# Schematics_EasyEDA.net
KiCad netlist of a schematic drawn in EasyEDA
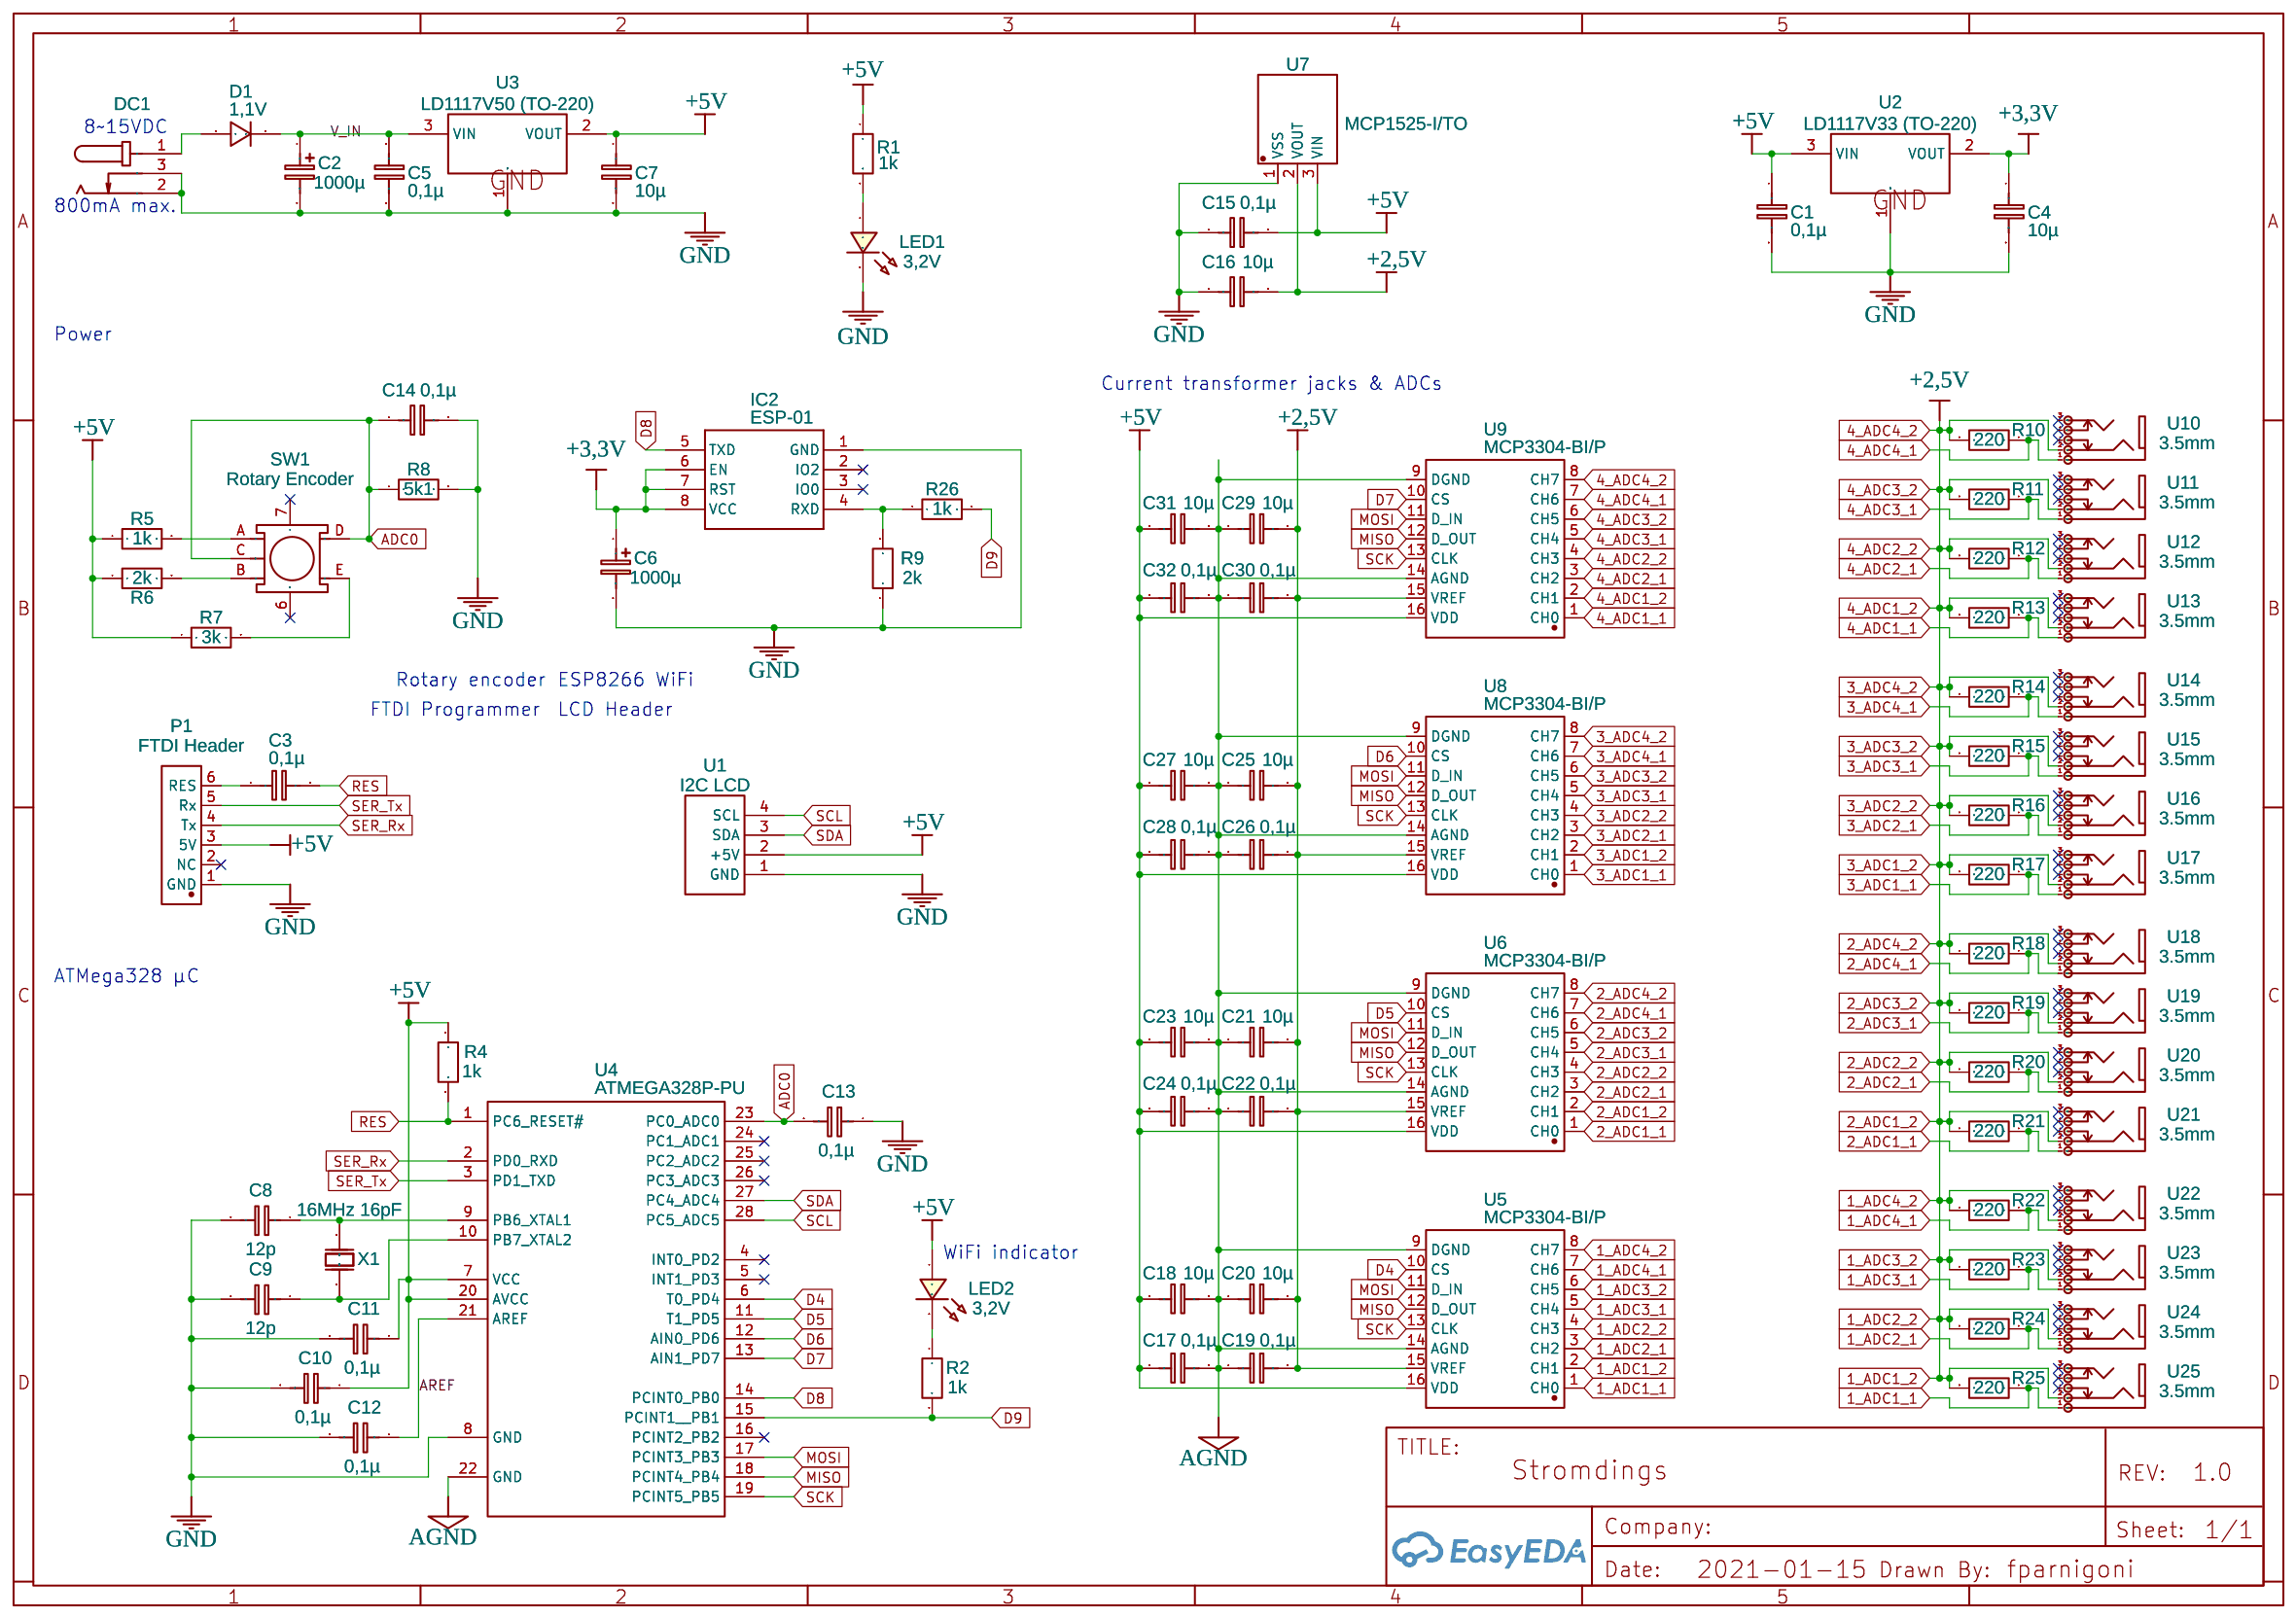
[diagram p0: schematic sheet]

(export (version "E")
  (design (tool "Eeschema 10.0.6"))
  (components
    (comp (ref "C1") (value "0,1µ") (libsource (lib "") (part "C_0603_EU_6")))
    (comp (ref "C2") (value "1000µ") (libsource (lib "") (part "C_Tan_SMD_A_EU_1")))
    (comp (ref "C3") (value "0,1µ") (libsource (lib "") (part "C_0603_EU_5")))
    (comp (ref "C4") (value "10µ") (libsource (lib "") (part "C_0603_EU_6")))
    (comp (ref "C5") (value "0,1µ") (libsource (lib "") (part "C_0603_EU_7")))
    (comp (ref "C6") (value "1000µ") (libsource (lib "") (part "C_Tan_SMD_A_EU")))
    (comp (ref "C7") (value "10µ") (libsource (lib "") (part "C_0603_EU_7")))
    (comp (ref "C8") (value "12p") (libsource (lib "") (part "C_0603_EU_2")))
    (comp (ref "C9") (value "12p") (libsource (lib "") (part "C_0603_EU_2")))
    (comp (ref "C10") (value "0,1µ") (libsource (lib "") (part "C_0603_EU_8")))
    (comp (ref "C11") (value "0,1µ") (libsource (lib "") (part "C_0603_EU_3")))
    (comp (ref "C12") (value "0,1µ") (libsource (lib "") (part "C_0603_EU_8")))
    (comp (ref "C13") (value "0,1µ") (libsource (lib "") (part "C_0603_EU_3")))
    (comp (ref "C14") (value "0,1µ") (libsource (lib "") (part "C_0603_EU_4")))
    (comp (ref "C15") (value "0,1µ") (libsource (lib "") (part "C_0603_EU_1")))
    (comp (ref "C16") (value "10µ") (libsource (lib "") (part "C_0603_EU_1")))
    (comp (ref "C17") (value "0,1µ") (libsource (lib "") (part "C_0603_EU_1")))
    (comp (ref "C18") (value "10µ") (libsource (lib "") (part "C_0603_EU")))
    (comp (ref "C19") (value "0,1µ") (libsource (lib "") (part "C_0603_EU_1")))
    (comp (ref "C20") (value "10µ") (libsource (lib "") (part "C_0603_EU")))
    (comp (ref "C21") (value "10µ") (libsource (lib "") (part "C_0603_EU")))
    (comp (ref "C22") (value "0,1µ") (libsource (lib "") (part "C_0603_EU")))
    (comp (ref "C23") (value "10µ") (libsource (lib "") (part "C_0603_EU")))
    (comp (ref "C24") (value "0,1µ") (libsource (lib "") (part "C_0603_EU")))
    (comp (ref "C25") (value "10µ") (libsource (lib "") (part "C_0603_EU")))
    (comp (ref "C26") (value "0,1µ") (libsource (lib "") (part "C_0603_EU")))
    (comp (ref "C27") (value "10µ") (libsource (lib "") (part "C_0603_EU")))
    (comp (ref "C28") (value "0,1µ") (libsource (lib "") (part "C_0603_EU")))
    (comp (ref "C29") (value "10µ") (libsource (lib "") (part "C_0603_EU_1")))
    (comp (ref "C30") (value "0,1µ") (libsource (lib "") (part "C_0603_EU")))
    (comp (ref "C31") (value "10µ") (libsource (lib "") (part "C_0603_EU_1")))
    (comp (ref "C32") (value "0,1µ") (libsource (lib "") (part "C_0603_EU")))
    (comp (ref "D1")
      (value "1,1V")
      (fields (field (name "BOM_Manufacturer Part") "1N4007W") (field (name "BOM_Supplier Part") "C328592"))
      (libsource (lib "") (part "1N4007W"))
    )
    (comp (ref "DC1")
      (value "DC005-2.0MM")
      (fields (field (name "BOM_Supplier Part") "C111567"))
      (libsource (lib "") (part "DC005-2.0MM"))
    )
    (comp (ref "IC2") (value "ESP-01") (libsource (lib "") (part "ESP-01")))
    (comp (ref "LED1")
      (value "3,2V")
      (fields
        (field (name "BOM_Manufacturer Part") "D-B080508B1-KS2")
        (field (name "BOM_Supplier Part") "C108412")
      )
      (libsource (lib "") (part "LED-0805_B"))
    )
    (comp (ref "LED2")
      (value "3,2V")
      (fields
        (field (name "BOM_Manufacturer Part") "D-B080508B1-KS2")
        (field (name "BOM_Supplier Part") "C108412")
      )
      (libsource (lib "") (part "LED-0805_B"))
    )
    (comp (ref "P1")
      (value "FTDI Header")
      (fields
        (field (name "BOM_Manufacturer Part") "Female header 1*6p")
        (field (name "BOM_Supplier Part") "C40877")
      )
      (libsource (lib "") (part "Header-Female-2.54_1x6"))
    )
    (comp (ref "R1") (value "1k") (libsource (lib "") (part "R_0603_EU_2")))
    (comp (ref "R2") (value "1k") (libsource (lib "") (part "R_0603_EU_2")))
    (comp (ref "R4") (value "1k") (libsource (lib "") (part "R_0603_EU_2")))
    (comp (ref "R5") (value "1k") (libsource (lib "") (part "R_0603_EU")))
    (comp (ref "R6") (value "2k") (libsource (lib "") (part "R_0603_EU")))
    (comp (ref "R7") (value "3k") (libsource (lib "") (part "R_0603_EU")))
    (comp (ref "R8") (value "5k1") (libsource (lib "") (part "R_0603_EU")))
    (comp (ref "R9") (value "2k") (libsource (lib "") (part "R_0603_EU_3")))
    (comp (ref "R10") (value "220") (libsource (lib "") (part "R_0603_EU_1")))
    (comp (ref "R11") (value "220") (libsource (lib "") (part "R_0603_EU_1")))
    (comp (ref "R12") (value "220") (libsource (lib "") (part "R_0603_EU_1")))
    (comp (ref "R13") (value "220") (libsource (lib "") (part "R_0603_EU_1")))
    (comp (ref "R14") (value "220") (libsource (lib "") (part "R_0603_EU_1")))
    (comp (ref "R15") (value "220") (libsource (lib "") (part "R_0603_EU_1")))
    (comp (ref "R16") (value "220") (libsource (lib "") (part "R_0603_EU_1")))
    (comp (ref "R17") (value "220") (libsource (lib "") (part "R_0603_EU_1")))
    (comp (ref "R18") (value "220") (libsource (lib "") (part "R_0603_EU_1")))
    (comp (ref "R19") (value "220") (libsource (lib "") (part "R_0603_EU_1")))
    (comp (ref "R20") (value "220") (libsource (lib "") (part "R_0603_EU_1")))
    (comp (ref "R21") (value "220") (libsource (lib "") (part "R_0603_EU_1")))
    (comp (ref "R22") (value "220") (libsource (lib "") (part "R_0603_EU_1")))
    (comp (ref "R23") (value "220") (libsource (lib "") (part "R_0603_EU_1")))
    (comp (ref "R24") (value "220") (libsource (lib "") (part "R_0603_EU_1")))
    (comp (ref "R25") (value "220") (libsource (lib "") (part "R_0603_EU_1")))
    (comp (ref "R26") (value "1k") (libsource (lib "") (part "R_0603_EU")))
    (comp (ref "SW1")
      (value "Rotary Encoder")
      (fields
        (field (name "BOM_Manufacturer Part") "EC11E09244BS")
        (field (name "BOM_Supplier Part") "C470742")
      )
      (libsource (lib "") (part "EC11E09244BS"))
    )
    (comp (ref "U1") (value "I2C LCD") (libsource (lib "") (part "I2C LCD")))
    (comp (ref "U2")
      (value "LD1117V33 (TO-220)")
      (fields (field (name "BOM_Manufacturer Part") "LD1117V33") (field (name "BOM_Supplier Part") "C283467"))
      (libsource (lib "") (part "LD1117V33"))
    )
    (comp (ref "U3")
      (value "LD1117V50 (TO-220)")
      (fields (field (name "BOM_Manufacturer Part") "LD1117V33") (field (name "BOM_Supplier Part") "C283467"))
      (libsource (lib "") (part "LD1117V33"))
    )
    (comp (ref "U4")
      (value "ATMEGA328P-PU")
      (fields (field (name "BOM_Supplier Part") "C33901"))
      (libsource (lib "") (part "ATMEGA328P-PU"))
    )
    (comp (ref "U5") (value "MCP3304-BI/P") (libsource (lib "") (part "MCP3304-BI/P")))
    (comp (ref "U6") (value "MCP3304-BI/P") (libsource (lib "") (part "MCP3304-BI/P")))
    (comp (ref "U7")
      (value "MCP1525-I/TO")
      (fields (field (name "BOM_Supplier Part") "C184389"))
      (libsource (lib "") (part "MCP1525-I/TO"))
    )
    (comp (ref "U8") (value "MCP3304-BI/P") (libsource (lib "") (part "MCP3304-BI/P")))
    (comp (ref "U9") (value "MCP3304-BI/P") (libsource (lib "") (part "MCP3304-BI/P")))
    (comp (ref "U10") (value "3.5mm") (libsource (lib "") (part "Unknown_1060_-590")))
    (comp (ref "U11") (value "3.5mm") (libsource (lib "") (part "Unknown_1060_-560")))
    (comp (ref "U12") (value "3.5mm") (libsource (lib "") (part "Unknown_1060_-530")))
    (comp (ref "U13") (value "3.5mm") (libsource (lib "") (part "Unknown_1060_-500")))
    (comp (ref "U14") (value "3.5mm") (libsource (lib "") (part "Unknown_1060_-460")))
    (comp (ref "U15") (value "3.5mm") (libsource (lib "") (part "Unknown_1060_-430")))
    (comp (ref "U16") (value "3.5mm") (libsource (lib "") (part "Unknown_1060_-400")))
    (comp (ref "U17") (value "3.5mm") (libsource (lib "") (part "Unknown_1060_-370")))
    (comp (ref "U18") (value "3.5mm") (libsource (lib "") (part "Unknown_1060_-330")))
    (comp (ref "U19") (value "3.5mm") (libsource (lib "") (part "Unknown_1060_-300")))
    (comp (ref "U20") (value "3.5mm") (libsource (lib "") (part "Unknown_1060_-270")))
    (comp (ref "U21") (value "3.5mm") (libsource (lib "") (part "Unknown_1060_-240")))
    (comp (ref "U22") (value "3.5mm") (libsource (lib "") (part "Unknown_1060_-200")))
    (comp (ref "U23") (value "3.5mm") (libsource (lib "") (part "Unknown_1060_-170")))
    (comp (ref "U24") (value "3.5mm") (libsource (lib "") (part "Unknown_1060_-140")))
    (comp (ref "U25") (value "3.5mm") (libsource (lib "") (part "Unknown_1060_-110")))
    (comp (ref "X1")
      (value "16MHz 16pF")
      (fields
        (field (name "BOM_Manufacturer Part") "HCM4916000000ABJT")
        (field (name "BOM_Supplier Part") "C326544")
      )
      (libsource (lib "") (part "HCM4916000000ABJT"))
    )
  )
  (nets
    (net (code "1") (name "+3,3V") (class "Default")
      (node (ref "C4") (pin "1") (pinfunction "1_1") (pintype "unspecified"))
      (node (ref "C6") (pin "1") (pinfunction "1_1") (pintype "unspecified"))
      (node (ref "IC2") (pin "6") (pinfunction "EN_6") (pintype "bidirectional"))
      (node (ref "IC2") (pin "7") (pinfunction "RST_7") (pintype "bidirectional"))
      (node (ref "IC2") (pin "8") (pinfunction "VCC_8") (pintype "bidirectional"))
      (node (ref "U2") (pin "2") (pinfunction "VOUT_2") (pintype "passive"))
    )
    (net (code "2") (name "+5V") (class "Default")
      (node (ref "C1") (pin "1") (pinfunction "1_1") (pintype "unspecified"))
      (node (ref "C10") (pin "1") (pinfunction "1_1") (pintype "unspecified"))
      (node (ref "C11") (pin "1") (pinfunction "1_1") (pintype "unspecified"))
      (node (ref "C15") (pin "2") (pinfunction "2_2") (pintype "unspecified"))
      (node (ref "C17") (pin "1") (pinfunction "1_1") (pintype "unspecified"))
      (node (ref "C18") (pin "1") (pinfunction "1_1") (pintype "unspecified"))
      (node (ref "C23") (pin "1") (pinfunction "1_1") (pintype "unspecified"))
      (node (ref "C24") (pin "1") (pinfunction "1_1") (pintype "unspecified"))
      (node (ref "C27") (pin "1") (pinfunction "1_1") (pintype "unspecified"))
      (node (ref "C28") (pin "1") (pinfunction "1_1") (pintype "unspecified"))
      (node (ref "C31") (pin "1") (pinfunction "1_1") (pintype "unspecified"))
      (node (ref "C32") (pin "1") (pinfunction "1_1") (pintype "unspecified"))
      (node (ref "C7") (pin "1") (pinfunction "1_1") (pintype "unspecified"))
      (node (ref "LED2") (pin "1") (pinfunction "1_1") (pintype "unspecified"))
      (node (ref "P1") (pin "3") (pinfunction "5V_3") (pintype "unspecified"))
      (node (ref "R1") (pin "1") (pinfunction "1_1") (pintype "unspecified"))
      (node (ref "R4") (pin "1") (pinfunction "1_1") (pintype "unspecified"))
      (node (ref "R5") (pin "1") (pinfunction "1_1") (pintype "unspecified"))
      (node (ref "R6") (pin "1") (pinfunction "1_1") (pintype "unspecified"))
      (node (ref "R7") (pin "1") (pinfunction "1_1") (pintype "unspecified"))
      (node (ref "U1") (pin "2") (pinfunction "+5V_2") (pintype "unspecified"))
      (node (ref "U2") (pin "3") (pinfunction "VIN_3") (pintype "passive"))
      (node (ref "U3") (pin "2") (pinfunction "VOUT_2") (pintype "passive"))
      (node (ref "U4") (pin "20") (pinfunction "AVCC_20") (pintype "passive"))
      (node (ref "U4") (pin "7") (pinfunction "VCC_7") (pintype "passive"))
      (node (ref "U5") (pin "16") (pinfunction "VDD_16") (pintype "unspecified"))
      (node (ref "U6") (pin "16") (pinfunction "VDD_16") (pintype "unspecified"))
      (node (ref "U7") (pin "3") (pinfunction "VIN_3") (pintype "unspecified"))
      (node (ref "U8") (pin "16") (pinfunction "VDD_16") (pintype "unspecified"))
      (node (ref "U9") (pin "16") (pinfunction "VDD_16") (pintype "unspecified"))
    )
    (net (code "3") (name "/AREF") (class "Default")
      (node (ref "C12") (pin "1") (pinfunction "1_1") (pintype "unspecified"))
      (node (ref "U4") (pin "21") (pinfunction "AREF_21") (pintype "passive"))
    )
    (net (code "4") (name "/V_IN") (class "Default")
      (node (ref "C2") (pin "1") (pinfunction "1_1") (pintype "unspecified"))
      (node (ref "C5") (pin "1") (pinfunction "1_1") (pintype "unspecified"))
      (node (ref "D1") (pin "1") (pinfunction "1_1") (pintype "unspecified"))
      (node (ref "U3") (pin "3") (pinfunction "VIN_3") (pintype "passive"))
    )
    (net (code "5") (name "1_ADC1_1") (class "Default")
      (node (ref "R25") (pin "1") (pinfunction "1_1") (pintype "unspecified"))
      (node (ref "U25") (pin "1") (pinfunction "SLV_1") (pintype "input"))
      (node (ref "U5") (pin "1") (pinfunction "CH0_1") (pintype "unspecified"))
    )
    (net (code "6") (name "1_ADC1_2") (class "Default")
      (node (ref "C16") (pin "2") (pinfunction "2_2") (pintype "unspecified"))
      (node (ref "C19") (pin "2") (pinfunction "2_2") (pintype "unspecified"))
      (node (ref "C20") (pin "2") (pinfunction "2_2") (pintype "unspecified"))
      (node (ref "C21") (pin "2") (pinfunction "2_2") (pintype "unspecified"))
      (node (ref "C22") (pin "2") (pinfunction "2_2") (pintype "unspecified"))
      (node (ref "C25") (pin "2") (pinfunction "2_2") (pintype "unspecified"))
      (node (ref "C26") (pin "2") (pinfunction "2_2") (pintype "unspecified"))
      (node (ref "C29") (pin "2") (pinfunction "2_2") (pintype "unspecified"))
      (node (ref "C30") (pin "2") (pinfunction "2_2") (pintype "unspecified"))
      (node (ref "R10") (pin "2") (pinfunction "2_2") (pintype "unspecified"))
      (node (ref "R11") (pin "2") (pinfunction "2_2") (pintype "unspecified"))
      (node (ref "R12") (pin "2") (pinfunction "2_2") (pintype "unspecified"))
      (node (ref "R13") (pin "2") (pinfunction "2_2") (pintype "unspecified"))
      (node (ref "R14") (pin "2") (pinfunction "2_2") (pintype "unspecified"))
      (node (ref "R15") (pin "2") (pinfunction "2_2") (pintype "unspecified"))
      (node (ref "R16") (pin "2") (pinfunction "2_2") (pintype "unspecified"))
      (node (ref "R17") (pin "2") (pinfunction "2_2") (pintype "unspecified"))
      (node (ref "R18") (pin "2") (pinfunction "2_2") (pintype "unspecified"))
      (node (ref "R19") (pin "2") (pinfunction "2_2") (pintype "unspecified"))
      (node (ref "R20") (pin "2") (pinfunction "2_2") (pintype "unspecified"))
      (node (ref "R21") (pin "2") (pinfunction "2_2") (pintype "unspecified"))
      (node (ref "R22") (pin "2") (pinfunction "2_2") (pintype "unspecified"))
      (node (ref "R23") (pin "2") (pinfunction "2_2") (pintype "unspecified"))
      (node (ref "R24") (pin "2") (pinfunction "2_2") (pintype "unspecified"))
      (node (ref "R25") (pin "2") (pinfunction "2_2") (pintype "unspecified"))
      (node (ref "U10") (pin "2") (pinfunction "TIP_2") (pintype "input"))
      (node (ref "U11") (pin "2") (pinfunction "TIP_2") (pintype "input"))
      (node (ref "U12") (pin "2") (pinfunction "TIP_2") (pintype "input"))
      (node (ref "U13") (pin "2") (pinfunction "TIP_2") (pintype "input"))
      (node (ref "U14") (pin "2") (pinfunction "TIP_2") (pintype "input"))
      (node (ref "U15") (pin "2") (pinfunction "TIP_2") (pintype "input"))
      (node (ref "U16") (pin "2") (pinfunction "TIP_2") (pintype "input"))
      (node (ref "U17") (pin "2") (pinfunction "TIP_2") (pintype "input"))
      (node (ref "U18") (pin "2") (pinfunction "TIP_2") (pintype "input"))
      (node (ref "U19") (pin "2") (pinfunction "TIP_2") (pintype "input"))
      (node (ref "U20") (pin "2") (pinfunction "TIP_2") (pintype "input"))
      (node (ref "U21") (pin "2") (pinfunction "TIP_2") (pintype "input"))
      (node (ref "U22") (pin "2") (pinfunction "TIP_2") (pintype "input"))
      (node (ref "U23") (pin "2") (pinfunction "TIP_2") (pintype "input"))
      (node (ref "U24") (pin "2") (pinfunction "TIP_2") (pintype "input"))
      (node (ref "U25") (pin "2") (pinfunction "TIP_2") (pintype "input"))
      (node (ref "U5") (pin "15") (pinfunction "VREF_15") (pintype "unspecified"))
      (node (ref "U5") (pin "2") (pinfunction "CH1_2") (pintype "unspecified"))
      (node (ref "U5") (pin "4") (pinfunction "CH3_4") (pintype "unspecified"))
      (node (ref "U5") (pin "6") (pinfunction "CH5_6") (pintype "unspecified"))
      (node (ref "U5") (pin "8") (pinfunction "CH7_8") (pintype "unspecified"))
      (node (ref "U6") (pin "15") (pinfunction "VREF_15") (pintype "unspecified"))
      (node (ref "U6") (pin "2") (pinfunction "CH1_2") (pintype "unspecified"))
      (node (ref "U6") (pin "4") (pinfunction "CH3_4") (pintype "unspecified"))
      (node (ref "U6") (pin "6") (pinfunction "CH5_6") (pintype "unspecified"))
      (node (ref "U6") (pin "8") (pinfunction "CH7_8") (pintype "unspecified"))
      (node (ref "U7") (pin "2") (pinfunction "VOUT_2") (pintype "unspecified"))
      (node (ref "U8") (pin "15") (pinfunction "VREF_15") (pintype "unspecified"))
      (node (ref "U8") (pin "2") (pinfunction "CH1_2") (pintype "unspecified"))
      (node (ref "U8") (pin "4") (pinfunction "CH3_4") (pintype "unspecified"))
      (node (ref "U8") (pin "6") (pinfunction "CH5_6") (pintype "unspecified"))
      (node (ref "U8") (pin "8") (pinfunction "CH7_8") (pintype "unspecified"))
      (node (ref "U9") (pin "15") (pinfunction "VREF_15") (pintype "unspecified"))
      (node (ref "U9") (pin "2") (pinfunction "CH1_2") (pintype "unspecified"))
      (node (ref "U9") (pin "4") (pinfunction "CH3_4") (pintype "unspecified"))
      (node (ref "U9") (pin "6") (pinfunction "CH5_6") (pintype "unspecified"))
      (node (ref "U9") (pin "8") (pinfunction "CH7_8") (pintype "unspecified"))
    )
    (net (code "7") (name "1_ADC2_1") (class "Default")
      (node (ref "R24") (pin "1") (pinfunction "1_1") (pintype "unspecified"))
      (node (ref "U24") (pin "1") (pinfunction "SLV_1") (pintype "input"))
      (node (ref "U5") (pin "3") (pinfunction "CH2_3") (pintype "unspecified"))
    )
    (net (code "8") (name "1_ADC3_1") (class "Default")
      (node (ref "R23") (pin "1") (pinfunction "1_1") (pintype "unspecified"))
      (node (ref "U23") (pin "1") (pinfunction "SLV_1") (pintype "input"))
      (node (ref "U5") (pin "5") (pinfunction "CH4_5") (pintype "unspecified"))
    )
    (net (code "9") (name "1_ADC4_1") (class "Default")
      (node (ref "R22") (pin "1") (pinfunction "1_1") (pintype "unspecified"))
      (node (ref "U22") (pin "1") (pinfunction "SLV_1") (pintype "input"))
      (node (ref "U5") (pin "7") (pinfunction "CH6_7") (pintype "unspecified"))
    )
    (net (code "10") (name "2_ADC1_1") (class "Default")
      (node (ref "R21") (pin "1") (pinfunction "1_1") (pintype "unspecified"))
      (node (ref "U21") (pin "1") (pinfunction "SLV_1") (pintype "input"))
      (node (ref "U6") (pin "1") (pinfunction "CH0_1") (pintype "unspecified"))
    )
    (net (code "11") (name "2_ADC2_1") (class "Default")
      (node (ref "R20") (pin "1") (pinfunction "1_1") (pintype "unspecified"))
      (node (ref "U20") (pin "1") (pinfunction "SLV_1") (pintype "input"))
      (node (ref "U6") (pin "3") (pinfunction "CH2_3") (pintype "unspecified"))
    )
    (net (code "12") (name "2_ADC3_1") (class "Default")
      (node (ref "R19") (pin "1") (pinfunction "1_1") (pintype "unspecified"))
      (node (ref "U19") (pin "1") (pinfunction "SLV_1") (pintype "input"))
      (node (ref "U6") (pin "5") (pinfunction "CH4_5") (pintype "unspecified"))
    )
    (net (code "13") (name "2_ADC4_1") (class "Default")
      (node (ref "R18") (pin "1") (pinfunction "1_1") (pintype "unspecified"))
      (node (ref "U18") (pin "1") (pinfunction "SLV_1") (pintype "input"))
      (node (ref "U6") (pin "7") (pinfunction "CH6_7") (pintype "unspecified"))
    )
    (net (code "14") (name "3_ADC1_1") (class "Default")
      (node (ref "R17") (pin "1") (pinfunction "1_1") (pintype "unspecified"))
      (node (ref "U17") (pin "1") (pinfunction "SLV_1") (pintype "input"))
      (node (ref "U8") (pin "1") (pinfunction "CH0_1") (pintype "unspecified"))
    )
    (net (code "15") (name "3_ADC2_1") (class "Default")
      (node (ref "R16") (pin "1") (pinfunction "1_1") (pintype "unspecified"))
      (node (ref "U16") (pin "1") (pinfunction "SLV_1") (pintype "input"))
      (node (ref "U8") (pin "3") (pinfunction "CH2_3") (pintype "unspecified"))
    )
    (net (code "16") (name "3_ADC3_1") (class "Default")
      (node (ref "R15") (pin "1") (pinfunction "1_1") (pintype "unspecified"))
      (node (ref "U15") (pin "1") (pinfunction "SLV_1") (pintype "input"))
      (node (ref "U8") (pin "5") (pinfunction "CH4_5") (pintype "unspecified"))
    )
    (net (code "17") (name "3_ADC4_1") (class "Default")
      (node (ref "R14") (pin "1") (pinfunction "1_1") (pintype "unspecified"))
      (node (ref "U14") (pin "1") (pinfunction "SLV_1") (pintype "input"))
      (node (ref "U8") (pin "7") (pinfunction "CH6_7") (pintype "unspecified"))
    )
    (net (code "18") (name "4_ADC1_1") (class "Default")
      (node (ref "R13") (pin "1") (pinfunction "1_1") (pintype "unspecified"))
      (node (ref "U13") (pin "1") (pinfunction "SLV_1") (pintype "input"))
      (node (ref "U9") (pin "1") (pinfunction "CH0_1") (pintype "unspecified"))
    )
    (net (code "19") (name "4_ADC2_1") (class "Default")
      (node (ref "R12") (pin "1") (pinfunction "1_1") (pintype "unspecified"))
      (node (ref "U12") (pin "1") (pinfunction "SLV_1") (pintype "input"))
      (node (ref "U9") (pin "3") (pinfunction "CH2_3") (pintype "unspecified"))
    )
    (net (code "20") (name "4_ADC3_1") (class "Default")
      (node (ref "R11") (pin "1") (pinfunction "1_1") (pintype "unspecified"))
      (node (ref "U11") (pin "1") (pinfunction "SLV_1") (pintype "input"))
      (node (ref "U9") (pin "5") (pinfunction "CH4_5") (pintype "unspecified"))
    )
    (net (code "21") (name "4_ADC4_1") (class "Default")
      (node (ref "R10") (pin "1") (pinfunction "1_1") (pintype "unspecified"))
      (node (ref "U10") (pin "1") (pinfunction "SLV_1") (pintype "input"))
      (node (ref "U9") (pin "7") (pinfunction "CH6_7") (pintype "unspecified"))
    )
    (net (code "22") (name "ADC0") (class "Default")
      (node (ref "C13") (pin "2") (pinfunction "2_2") (pintype "unspecified"))
      (node (ref "C14") (pin "1") (pinfunction "1_1") (pintype "unspecified"))
      (node (ref "R8") (pin "1") (pinfunction "1_1") (pintype "unspecified"))
      (node (ref "SW1") (pin "C") (pinfunction "C_C") (pintype "unspecified"))
      (node (ref "SW1") (pin "D") (pinfunction "D_D") (pintype "unspecified"))
      (node (ref "U4") (pin "23") (pinfunction "PC0_ADC0_23") (pintype "bidirectional"))
    )
    (net (code "23") (name "AGND") (class "Default")
      (node (ref "C17") (pin "2") (pinfunction "2_2") (pintype "unspecified"))
      (node (ref "C18") (pin "2") (pinfunction "2_2") (pintype "unspecified"))
      (node (ref "C19") (pin "1") (pinfunction "1_1") (pintype "unspecified"))
      (node (ref "C20") (pin "1") (pinfunction "1_1") (pintype "unspecified"))
      (node (ref "C21") (pin "1") (pinfunction "1_1") (pintype "unspecified"))
      (node (ref "C22") (pin "1") (pinfunction "1_1") (pintype "unspecified"))
      (node (ref "C23") (pin "2") (pinfunction "2_2") (pintype "unspecified"))
      (node (ref "C24") (pin "2") (pinfunction "2_2") (pintype "unspecified"))
      (node (ref "C25") (pin "1") (pinfunction "1_1") (pintype "unspecified"))
      (node (ref "C26") (pin "1") (pinfunction "1_1") (pintype "unspecified"))
      (node (ref "C27") (pin "2") (pinfunction "2_2") (pintype "unspecified"))
      (node (ref "C28") (pin "2") (pinfunction "2_2") (pintype "unspecified"))
      (node (ref "C29") (pin "1") (pinfunction "1_1") (pintype "unspecified"))
      (node (ref "C30") (pin "1") (pinfunction "1_1") (pintype "unspecified"))
      (node (ref "C31") (pin "2") (pinfunction "2_2") (pintype "unspecified"))
      (node (ref "C32") (pin "2") (pinfunction "2_2") (pintype "unspecified"))
      (node (ref "U4") (pin "22") (pinfunction "GND_22") (pintype "passive"))
      (node (ref "U5") (pin "14") (pinfunction "AGND_14") (pintype "unspecified"))
      (node (ref "U5") (pin "9") (pinfunction "DGND_9") (pintype "unspecified"))
      (node (ref "U6") (pin "14") (pinfunction "AGND_14") (pintype "unspecified"))
      (node (ref "U6") (pin "9") (pinfunction "DGND_9") (pintype "unspecified"))
      (node (ref "U8") (pin "14") (pinfunction "AGND_14") (pintype "unspecified"))
      (node (ref "U8") (pin "9") (pinfunction "DGND_9") (pintype "unspecified"))
      (node (ref "U9") (pin "14") (pinfunction "AGND_14") (pintype "unspecified"))
      (node (ref "U9") (pin "9") (pinfunction "DGND_9") (pintype "unspecified"))
    )
    (net (code "24") (name "D4") (class "Default")
      (node (ref "U4") (pin "6") (pinfunction "T0_PD4_6") (pintype "bidirectional"))
      (node (ref "U5") (pin "10") (pinfunction "CS_10") (pintype "unspecified"))
    )
    (net (code "25") (name "D5") (class "Default")
      (node (ref "U4") (pin "11") (pinfunction "T1_PD5_11") (pintype "bidirectional"))
      (node (ref "U6") (pin "10") (pinfunction "CS_10") (pintype "unspecified"))
    )
    (net (code "26") (name "D6") (class "Default")
      (node (ref "U4") (pin "12") (pinfunction "AIN0_PD6_12") (pintype "bidirectional"))
      (node (ref "U8") (pin "10") (pinfunction "CS_10") (pintype "unspecified"))
    )
    (net (code "27") (name "D7") (class "Default")
      (node (ref "U4") (pin "13") (pinfunction "AIN1_PD7_13") (pintype "bidirectional"))
      (node (ref "U9") (pin "10") (pinfunction "CS_10") (pintype "unspecified"))
    )
    (net (code "28") (name "D8") (class "Default")
      (node (ref "IC2") (pin "5") (pinfunction "TXD_5") (pintype "bidirectional"))
      (node (ref "U4") (pin "14") (pinfunction "PCINT0_PB0_14") (pintype "bidirectional"))
    )
    (net (code "29") (name "D9") (class "Default")
      (node (ref "R2") (pin "2") (pinfunction "2_2") (pintype "unspecified"))
      (node (ref "R26") (pin "2") (pinfunction "2_2") (pintype "unspecified"))
      (node (ref "U4") (pin "15") (pinfunction "PCINT1__PB1_15") (pintype "bidirectional"))
    )
    (net (code "30") (name "GND") (class "Default")
      (node (ref "C1") (pin "2") (pinfunction "2_2") (pintype "unspecified"))
      (node (ref "C10") (pin "2") (pinfunction "2_2") (pintype "unspecified"))
      (node (ref "C11") (pin "2") (pinfunction "2_2") (pintype "unspecified"))
      (node (ref "C12") (pin "2") (pinfunction "2_2") (pintype "unspecified"))
      (node (ref "C13") (pin "1") (pinfunction "1_1") (pintype "unspecified"))
      (node (ref "C14") (pin "2") (pinfunction "2_2") (pintype "unspecified"))
      (node (ref "C15") (pin "1") (pinfunction "1_1") (pintype "unspecified"))
      (node (ref "C16") (pin "1") (pinfunction "1_1") (pintype "unspecified"))
      (node (ref "C2") (pin "2") (pinfunction "2_2") (pintype "unspecified"))
      (node (ref "C4") (pin "2") (pinfunction "2_2") (pintype "unspecified"))
      (node (ref "C5") (pin "2") (pinfunction "2_2") (pintype "unspecified"))
      (node (ref "C6") (pin "2") (pinfunction "2_2") (pintype "unspecified"))
      (node (ref "C7") (pin "2") (pinfunction "2_2") (pintype "unspecified"))
      (node (ref "C8") (pin "2") (pinfunction "2_2") (pintype "unspecified"))
      (node (ref "C9") (pin "2") (pinfunction "2_2") (pintype "unspecified"))
      (node (ref "DC1") (pin "2") (pinfunction "2_2") (pintype "unspecified"))
      (node (ref "DC1") (pin "3") (pinfunction "3_3") (pintype "unspecified"))
      (node (ref "IC2") (pin "1") (pinfunction "GND_1") (pintype "bidirectional"))
      (node (ref "LED1") (pin "2") (pinfunction "2_2") (pintype "unspecified"))
      (node (ref "P1") (pin "1") (pinfunction "GND_1") (pintype "unspecified"))
      (node (ref "R8") (pin "2") (pinfunction "2_2") (pintype "unspecified"))
      (node (ref "R9") (pin "1") (pinfunction "1_1") (pintype "unspecified"))
      (node (ref "U1") (pin "1") (pinfunction "GND_1") (pintype "unspecified"))
      (node (ref "U2") (pin "1") (pinfunction "GND_1") (pintype "unspecified"))
      (node (ref "U3") (pin "1") (pinfunction "GND_1") (pintype "unspecified"))
      (node (ref "U4") (pin "8") (pinfunction "GND_8") (pintype "passive"))
      (node (ref "U7") (pin "1") (pinfunction "VSS_1") (pintype "unspecified"))
    )
    (net (code "31") (name "MISO") (class "Default")
      (node (ref "U4") (pin "18") (pinfunction "PCINT4_PB4_18") (pintype "bidirectional"))
      (node (ref "U5") (pin "12") (pinfunction "D_OUT_12") (pintype "unspecified"))
      (node (ref "U6") (pin "12") (pinfunction "D_OUT_12") (pintype "unspecified"))
      (node (ref "U8") (pin "12") (pinfunction "D_OUT_12") (pintype "unspecified"))
      (node (ref "U9") (pin "12") (pinfunction "D_OUT_12") (pintype "unspecified"))
    )
    (net (code "32") (name "MOSI") (class "Default")
      (node (ref "U4") (pin "17") (pinfunction "PCINT3_PB3_17") (pintype "bidirectional"))
      (node (ref "U5") (pin "11") (pinfunction "D_IN_11") (pintype "unspecified"))
      (node (ref "U6") (pin "11") (pinfunction "D_IN_11") (pintype "unspecified"))
      (node (ref "U8") (pin "11") (pinfunction "D_IN_11") (pintype "unspecified"))
      (node (ref "U9") (pin "11") (pinfunction "D_IN_11") (pintype "unspecified"))
    )
    (net (code "33") (name "Net-(D1-Pad2)") (class "Default")
      (node (ref "D1") (pin "2") (pinfunction "2_2") (pintype "unspecified"))
      (node (ref "DC1") (pin "1") (pinfunction "1_1") (pintype "unspecified"))
    )
    (net (code "34") (name "Net-(IC2-RXD)") (class "Default")
      (node (ref "IC2") (pin "4") (pinfunction "RXD_4") (pintype "bidirectional"))
      (node (ref "R26") (pin "1") (pinfunction "1_1") (pintype "unspecified"))
      (node (ref "R9") (pin "2") (pinfunction "2_2") (pintype "unspecified"))
    )
    (net (code "35") (name "Net-(LED1-Pad1)") (class "Default")
      (node (ref "LED1") (pin "1") (pinfunction "1_1") (pintype "unspecified"))
      (node (ref "R1") (pin "2") (pinfunction "2_2") (pintype "unspecified"))
    )
    (net (code "36") (name "Net-(LED2-Pad2)") (class "Default")
      (node (ref "LED2") (pin "2") (pinfunction "2_2") (pintype "unspecified"))
      (node (ref "R2") (pin "1") (pinfunction "1_1") (pintype "unspecified"))
    )
    (net (code "37") (name "Net-(P1-RES)") (class "Default")
      (node (ref "C3") (pin "1") (pinfunction "1_1") (pintype "unspecified"))
      (node (ref "P1") (pin "6") (pinfunction "RES_6") (pintype "unspecified"))
    )
    (net (code "38") (name "Net-(R5-Pad2)") (class "Default")
      (node (ref "R5") (pin "2") (pinfunction "2_2") (pintype "unspecified"))
      (node (ref "SW1") (pin "A") (pinfunction "A_A") (pintype "unspecified"))
    )
    (net (code "39") (name "Net-(R6-Pad2)") (class "Default")
      (node (ref "R6") (pin "2") (pinfunction "2_2") (pintype "unspecified"))
      (node (ref "SW1") (pin "B") (pinfunction "B_B") (pintype "unspecified"))
    )
    (net (code "40") (name "Net-(R7-Pad2)") (class "Default")
      (node (ref "R7") (pin "2") (pinfunction "2_2") (pintype "unspecified"))
      (node (ref "SW1") (pin "E") (pinfunction "E_E") (pintype "unspecified"))
    )
    (net (code "41") (name "Net-(U4-PB6_XTAL1)") (class "Default")
      (node (ref "C8") (pin "1") (pinfunction "1_1") (pintype "unspecified"))
      (node (ref "U4") (pin "9") (pinfunction "PB6_XTAL1_9") (pintype "bidirectional"))
      (node (ref "X1") (pin "2") (pinfunction "OSC2_2") (pintype "input"))
    )
    (net (code "42") (name "Net-(U4-PB7_XTAL2)") (class "Default")
      (node (ref "C9") (pin "1") (pinfunction "1_1") (pintype "unspecified"))
      (node (ref "U4") (pin "10") (pinfunction "PB7_XTAL2_10") (pintype "bidirectional"))
      (node (ref "X1") (pin "1") (pinfunction "OSC1_1") (pintype "input"))
    )
    (net (code "43") (name "RES") (class "Default")
      (node (ref "C3") (pin "2") (pinfunction "2_2") (pintype "unspecified"))
      (node (ref "R4") (pin "2") (pinfunction "2_2") (pintype "unspecified"))
      (node (ref "U4") (pin "1") (pinfunction "PC6_RESET#_1") (pintype "bidirectional"))
    )
    (net (code "44") (name "SCK") (class "Default")
      (node (ref "U4") (pin "19") (pinfunction "PCINT5_PB5_19") (pintype "bidirectional"))
      (node (ref "U5") (pin "13") (pinfunction "CLK_13") (pintype "unspecified"))
      (node (ref "U6") (pin "13") (pinfunction "CLK_13") (pintype "unspecified"))
      (node (ref "U8") (pin "13") (pinfunction "CLK_13") (pintype "unspecified"))
      (node (ref "U9") (pin "13") (pinfunction "CLK_13") (pintype "unspecified"))
    )
    (net (code "45") (name "SCL") (class "Default")
      (node (ref "U1") (pin "4") (pinfunction "SCL_4") (pintype "unspecified"))
      (node (ref "U4") (pin "28") (pinfunction "PC5_ADC5_28") (pintype "bidirectional"))
    )
    (net (code "46") (name "SDA") (class "Default")
      (node (ref "U1") (pin "3") (pinfunction "SDA_3") (pintype "unspecified"))
      (node (ref "U4") (pin "27") (pinfunction "PC4_ADC4_27") (pintype "bidirectional"))
    )
    (net (code "47") (name "SER_Rx") (class "Default")
      (node (ref "P1") (pin "4") (pinfunction "Tx_4") (pintype "unspecified"))
      (node (ref "U4") (pin "2") (pinfunction "PD0_RXD_2") (pintype "bidirectional"))
    )
    (net (code "48") (name "SER_Tx") (class "Default")
      (node (ref "P1") (pin "5") (pinfunction "Rx_5") (pintype "unspecified"))
      (node (ref "U4") (pin "3") (pinfunction "PD1_TXD_3") (pintype "bidirectional"))
    )
    (net (code "49") (name "unconnected-(IC2-IO0-Pad3)") (class "Default")
      (node (ref "IC2") (pin "3") (pinfunction "IO0_3") (pintype "bidirectional+no_connect"))
    )
    (net (code "50") (name "unconnected-(IC2-IO2-Pad2)") (class "Default")
      (node (ref "IC2") (pin "2") (pinfunction "IO2_2") (pintype "bidirectional+no_connect"))
    )
    (net (code "51") (name "unconnected-(P1-NC-Pad2)") (class "Default")
      (node (ref "P1") (pin "2") (pinfunction "NC_2") (pintype "unspecified+no_connect"))
    )
    (net (code "52") (name "unconnected-(SW1-Pad6)") (class "Default")
      (node (ref "SW1") (pin "6") (pinfunction "6_6") (pintype "unspecified+no_connect"))
    )
    (net (code "53") (name "unconnected-(SW1-Pad7)") (class "Default")
      (node (ref "SW1") (pin "7") (pinfunction "7_7") (pintype "unspecified+no_connect"))
    )
    (net (code "54") (name "unconnected-(U4-INT0_PD2-Pad4)") (class "Default")
      (node (ref "U4") (pin "4") (pinfunction "INT0_PD2_4") (pintype "bidirectional+no_connect"))
    )
    (net (code "55") (name "unconnected-(U4-INT1_PD3-Pad5)") (class "Default")
      (node (ref "U4") (pin "5") (pinfunction "INT1_PD3_5") (pintype "bidirectional+no_connect"))
    )
    (net (code "56") (name "unconnected-(U4-PC1_ADC1-Pad24)") (class "Default")
      (node (ref "U4") (pin "24") (pinfunction "PC1_ADC1_24") (pintype "bidirectional+no_connect"))
    )
    (net (code "57") (name "unconnected-(U4-PC2_ADC2-Pad25)") (class "Default")
      (node (ref "U4") (pin "25") (pinfunction "PC2_ADC2_25") (pintype "bidirectional+no_connect"))
    )
    (net (code "58") (name "unconnected-(U4-PC3_ADC3-Pad26)") (class "Default")
      (node (ref "U4") (pin "26") (pinfunction "PC3_ADC3_26") (pintype "bidirectional+no_connect"))
    )
    (net (code "59") (name "unconnected-(U4-PCINT2_PB2-Pad16)") (class "Default")
      (node (ref "U4") (pin "16") (pinfunction "PCINT2_PB2_16") (pintype "bidirectional+no_connect"))
    )
    (net (code "60") (name "unconnected-(U10-Pad4)") (class "Default")
      (node (ref "U10") (pin "4") (pinfunction "4_4") (pintype "input+no_connect"))
    )
    (net (code "61") (name "unconnected-(U10-Pad5)") (class "Default")
      (node (ref "U10") (pin "5") (pinfunction "5_5") (pintype "input+no_connect"))
    )
    (net (code "62") (name "unconnected-(U10-RNG-Pad3)") (class "Default")
      (node (ref "U10") (pin "3") (pinfunction "RNG_3") (pintype "input+no_connect"))
    )
    (net (code "63") (name "unconnected-(U11-Pad4)") (class "Default")
      (node (ref "U11") (pin "4") (pinfunction "4_4") (pintype "input+no_connect"))
    )
    (net (code "64") (name "unconnected-(U11-Pad5)") (class "Default")
      (node (ref "U11") (pin "5") (pinfunction "5_5") (pintype "input+no_connect"))
    )
    (net (code "65") (name "unconnected-(U11-RNG-Pad3)") (class "Default")
      (node (ref "U11") (pin "3") (pinfunction "RNG_3") (pintype "input+no_connect"))
    )
    (net (code "66") (name "unconnected-(U12-Pad4)") (class "Default")
      (node (ref "U12") (pin "4") (pinfunction "4_4") (pintype "input+no_connect"))
    )
    (net (code "67") (name "unconnected-(U12-Pad5)") (class "Default")
      (node (ref "U12") (pin "5") (pinfunction "5_5") (pintype "input+no_connect"))
    )
    (net (code "68") (name "unconnected-(U12-RNG-Pad3)") (class "Default")
      (node (ref "U12") (pin "3") (pinfunction "RNG_3") (pintype "input+no_connect"))
    )
    (net (code "69") (name "unconnected-(U13-Pad4)") (class "Default")
      (node (ref "U13") (pin "4") (pinfunction "4_4") (pintype "input+no_connect"))
    )
    (net (code "70") (name "unconnected-(U13-Pad5)") (class "Default")
      (node (ref "U13") (pin "5") (pinfunction "5_5") (pintype "input+no_connect"))
    )
    (net (code "71") (name "unconnected-(U13-RNG-Pad3)") (class "Default")
      (node (ref "U13") (pin "3") (pinfunction "RNG_3") (pintype "input+no_connect"))
    )
    (net (code "72") (name "unconnected-(U14-Pad4)") (class "Default")
      (node (ref "U14") (pin "4") (pinfunction "4_4") (pintype "input+no_connect"))
    )
    (net (code "73") (name "unconnected-(U14-Pad5)") (class "Default")
      (node (ref "U14") (pin "5") (pinfunction "5_5") (pintype "input+no_connect"))
    )
    (net (code "74") (name "unconnected-(U14-RNG-Pad3)") (class "Default")
      (node (ref "U14") (pin "3") (pinfunction "RNG_3") (pintype "input+no_connect"))
    )
    (net (code "75") (name "unconnected-(U15-Pad4)") (class "Default")
      (node (ref "U15") (pin "4") (pinfunction "4_4") (pintype "input+no_connect"))
    )
    (net (code "76") (name "unconnected-(U15-Pad5)") (class "Default")
      (node (ref "U15") (pin "5") (pinfunction "5_5") (pintype "input+no_connect"))
    )
    (net (code "77") (name "unconnected-(U15-RNG-Pad3)") (class "Default")
      (node (ref "U15") (pin "3") (pinfunction "RNG_3") (pintype "input+no_connect"))
    )
    (net (code "78") (name "unconnected-(U16-Pad4)") (class "Default")
      (node (ref "U16") (pin "4") (pinfunction "4_4") (pintype "input+no_connect"))
    )
    (net (code "79") (name "unconnected-(U16-Pad5)") (class "Default")
      (node (ref "U16") (pin "5") (pinfunction "5_5") (pintype "input+no_connect"))
    )
    (net (code "80") (name "unconnected-(U16-RNG-Pad3)") (class "Default")
      (node (ref "U16") (pin "3") (pinfunction "RNG_3") (pintype "input+no_connect"))
    )
    (net (code "81") (name "unconnected-(U17-Pad4)") (class "Default")
      (node (ref "U17") (pin "4") (pinfunction "4_4") (pintype "input+no_connect"))
    )
    (net (code "82") (name "unconnected-(U17-Pad5)") (class "Default")
      (node (ref "U17") (pin "5") (pinfunction "5_5") (pintype "input+no_connect"))
    )
    (net (code "83") (name "unconnected-(U17-RNG-Pad3)") (class "Default")
      (node (ref "U17") (pin "3") (pinfunction "RNG_3") (pintype "input+no_connect"))
    )
    (net (code "84") (name "unconnected-(U18-Pad4)") (class "Default")
      (node (ref "U18") (pin "4") (pinfunction "4_4") (pintype "input+no_connect"))
    )
    (net (code "85") (name "unconnected-(U18-Pad5)") (class "Default")
      (node (ref "U18") (pin "5") (pinfunction "5_5") (pintype "input+no_connect"))
    )
    (net (code "86") (name "unconnected-(U18-RNG-Pad3)") (class "Default")
      (node (ref "U18") (pin "3") (pinfunction "RNG_3") (pintype "input+no_connect"))
    )
    (net (code "87") (name "unconnected-(U19-Pad4)") (class "Default")
      (node (ref "U19") (pin "4") (pinfunction "4_4") (pintype "input+no_connect"))
    )
    (net (code "88") (name "unconnected-(U19-Pad5)") (class "Default")
      (node (ref "U19") (pin "5") (pinfunction "5_5") (pintype "input+no_connect"))
    )
    (net (code "89") (name "unconnected-(U19-RNG-Pad3)") (class "Default")
      (node (ref "U19") (pin "3") (pinfunction "RNG_3") (pintype "input+no_connect"))
    )
    (net (code "90") (name "unconnected-(U20-Pad4)") (class "Default")
      (node (ref "U20") (pin "4") (pinfunction "4_4") (pintype "input+no_connect"))
    )
    (net (code "91") (name "unconnected-(U20-Pad5)") (class "Default")
      (node (ref "U20") (pin "5") (pinfunction "5_5") (pintype "input+no_connect"))
    )
    (net (code "92") (name "unconnected-(U20-RNG-Pad3)") (class "Default")
      (node (ref "U20") (pin "3") (pinfunction "RNG_3") (pintype "input+no_connect"))
    )
    (net (code "93") (name "unconnected-(U21-Pad4)") (class "Default")
      (node (ref "U21") (pin "4") (pinfunction "4_4") (pintype "input+no_connect"))
    )
    (net (code "94") (name "unconnected-(U21-Pad5)") (class "Default")
      (node (ref "U21") (pin "5") (pinfunction "5_5") (pintype "input+no_connect"))
    )
    (net (code "95") (name "unconnected-(U21-RNG-Pad3)") (class "Default")
      (node (ref "U21") (pin "3") (pinfunction "RNG_3") (pintype "input+no_connect"))
    )
    (net (code "96") (name "unconnected-(U22-Pad4)") (class "Default")
      (node (ref "U22") (pin "4") (pinfunction "4_4") (pintype "input+no_connect"))
    )
    (net (code "97") (name "unconnected-(U22-Pad5)") (class "Default")
      (node (ref "U22") (pin "5") (pinfunction "5_5") (pintype "input+no_connect"))
    )
    (net (code "98") (name "unconnected-(U22-RNG-Pad3)") (class "Default")
      (node (ref "U22") (pin "3") (pinfunction "RNG_3") (pintype "input+no_connect"))
    )
    (net (code "99") (name "unconnected-(U23-Pad4)") (class "Default")
      (node (ref "U23") (pin "4") (pinfunction "4_4") (pintype "input+no_connect"))
    )
    (net (code "100") (name "unconnected-(U23-Pad5)") (class "Default")
      (node (ref "U23") (pin "5") (pinfunction "5_5") (pintype "input+no_connect"))
    )
    (net (code "101") (name "unconnected-(U23-RNG-Pad3)") (class "Default")
      (node (ref "U23") (pin "3") (pinfunction "RNG_3") (pintype "input+no_connect"))
    )
    (net (code "102") (name "unconnected-(U24-Pad4)") (class "Default")
      (node (ref "U24") (pin "4") (pinfunction "4_4") (pintype "input+no_connect"))
    )
    (net (code "103") (name "unconnected-(U24-Pad5)") (class "Default")
      (node (ref "U24") (pin "5") (pinfunction "5_5") (pintype "input+no_connect"))
    )
    (net (code "104") (name "unconnected-(U24-RNG-Pad3)") (class "Default")
      (node (ref "U24") (pin "3") (pinfunction "RNG_3") (pintype "input+no_connect"))
    )
    (net (code "105") (name "unconnected-(U25-Pad4)") (class "Default")
      (node (ref "U25") (pin "4") (pinfunction "4_4") (pintype "input+no_connect"))
    )
    (net (code "106") (name "unconnected-(U25-Pad5)") (class "Default")
      (node (ref "U25") (pin "5") (pinfunction "5_5") (pintype "input+no_connect"))
    )
    (net (code "107") (name "unconnected-(U25-RNG-Pad3)") (class "Default")
      (node (ref "U25") (pin "3") (pinfunction "RNG_3") (pintype "input+no_connect"))
    )
  )
)
